# SCH_tenth-portenta-stack_2023-01-13.net
KiCad netlist of a schematic drawn in EasyEDA
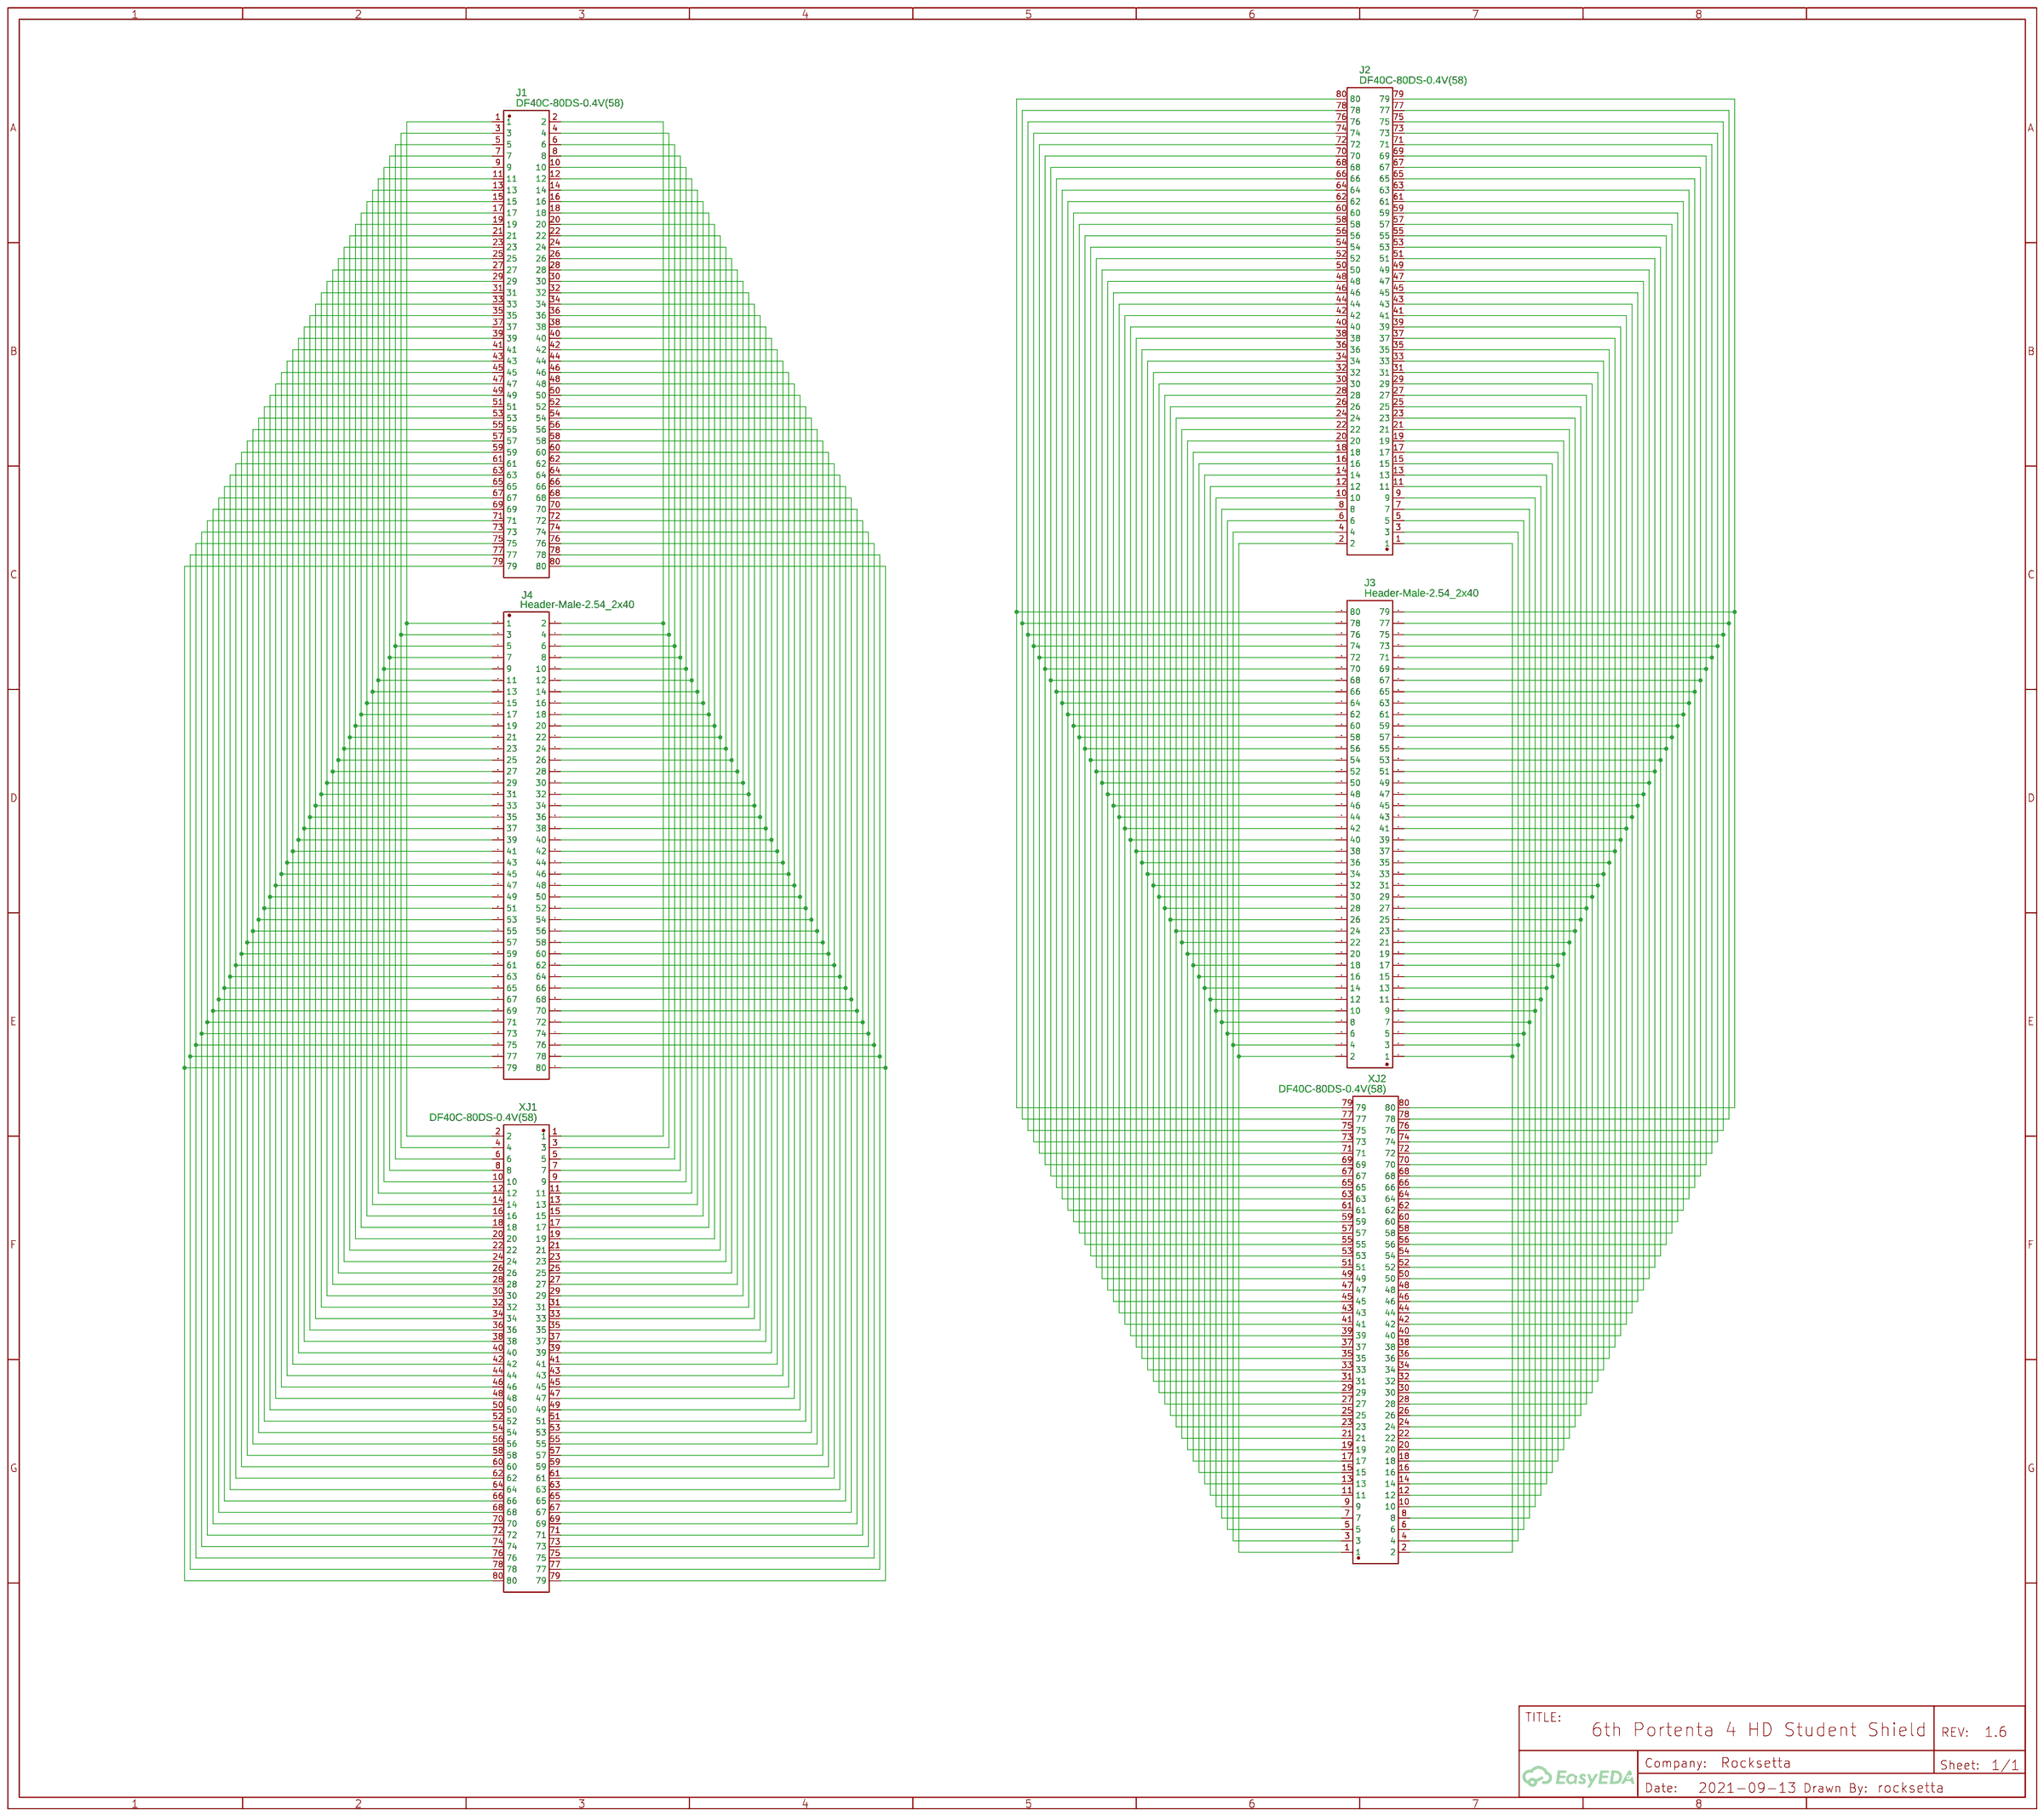
[diagram p0: schematic sheet]

(export (version "E")
  (design (tool "Eeschema 10.0.6"))
  (components
    (comp (ref "J1")
      (value "DF40C-80DS-0.4V(58)")
      (fields (field (name "BOM_Supplier Part") "C597941"))
      (libsource (lib "") (part "DF40C-80DS-0.4V(58)_1"))
    )
    (comp (ref "J2")
      (value "DF40C-80DS-0.4V(58)")
      (fields (field (name "BOM_Supplier Part") "C597941"))
      (libsource (lib "") (part "DF40C-80DS-0.4V(58)_2"))
    )
    (comp (ref "J3")
      (value "Header-Male-2.54_2x40")
      (fields
        (field (name "BOM_Manufacturer Part") "2.54mm 2x40P")
        (field (name "BOM_Supplier Part") "C2333")
      )
      (libsource (lib "") (part "Header-Male-2.54_2x40"))
    )
    (comp (ref "J4")
      (value "Header-Male-2.54_2x40")
      (fields
        (field (name "BOM_Manufacturer Part") "2.54mm 2x40P")
        (field (name "BOM_Supplier Part") "C2333")
      )
      (libsource (lib "") (part "Header-Male-2.54_2x40_1"))
    )
    (comp (ref "XJ1")
      (value "DF40C-80DS-0.4V(58)")
      (fields (field (name "BOM_Supplier Part") "C597941"))
      (libsource (lib "") (part "DF40C-80DS-0.4V(58)"))
    )
    (comp (ref "XJ2")
      (value "DF40C-80DS-0.4V(58)")
      (fields (field (name "BOM_Supplier Part") "C597941"))
      (libsource (lib "") (part "DF40C-80DS-0.4V(58)_3"))
    )
  )
  (nets
    (net (code "1") (name "Net-(J1-Pad1)") (class "Default")
      (node (ref "J1") (pin "1") (pinfunction "1_1") (pintype "unspecified"))
      (node (ref "J4") (pin "1") (pinfunction "1_1") (pintype "unspecified"))
      (node (ref "XJ1") (pin "2") (pinfunction "2_2") (pintype "unspecified"))
    )
    (net (code "2") (name "Net-(J1-Pad2)") (class "Default")
      (node (ref "J1") (pin "2") (pinfunction "2_2") (pintype "unspecified"))
      (node (ref "J4") (pin "2") (pinfunction "2_2") (pintype "unspecified"))
      (node (ref "XJ1") (pin "1") (pinfunction "1_1") (pintype "unspecified"))
    )
    (net (code "3") (name "Net-(J1-Pad3)") (class "Default")
      (node (ref "J1") (pin "3") (pinfunction "3_3") (pintype "unspecified"))
      (node (ref "J4") (pin "3") (pinfunction "3_3") (pintype "unspecified"))
      (node (ref "XJ1") (pin "4") (pinfunction "4_4") (pintype "unspecified"))
    )
    (net (code "4") (name "Net-(J1-Pad4)") (class "Default")
      (node (ref "J1") (pin "4") (pinfunction "4_4") (pintype "unspecified"))
      (node (ref "J4") (pin "4") (pinfunction "4_4") (pintype "unspecified"))
      (node (ref "XJ1") (pin "3") (pinfunction "3_3") (pintype "unspecified"))
    )
    (net (code "5") (name "Net-(J1-Pad5)") (class "Default")
      (node (ref "J1") (pin "5") (pinfunction "5_5") (pintype "unspecified"))
      (node (ref "J4") (pin "5") (pinfunction "5_5") (pintype "unspecified"))
      (node (ref "XJ1") (pin "6") (pinfunction "6_6") (pintype "unspecified"))
    )
    (net (code "6") (name "Net-(J1-Pad6)") (class "Default")
      (node (ref "J1") (pin "6") (pinfunction "6_6") (pintype "unspecified"))
      (node (ref "J4") (pin "6") (pinfunction "6_6") (pintype "unspecified"))
      (node (ref "XJ1") (pin "5") (pinfunction "5_5") (pintype "unspecified"))
    )
    (net (code "7") (name "Net-(J1-Pad7)") (class "Default")
      (node (ref "J1") (pin "7") (pinfunction "7_7") (pintype "unspecified"))
      (node (ref "J4") (pin "7") (pinfunction "7_7") (pintype "unspecified"))
      (node (ref "XJ1") (pin "8") (pinfunction "8_8") (pintype "unspecified"))
    )
    (net (code "8") (name "Net-(J1-Pad8)") (class "Default")
      (node (ref "J1") (pin "8") (pinfunction "8_8") (pintype "unspecified"))
      (node (ref "J4") (pin "8") (pinfunction "8_8") (pintype "unspecified"))
      (node (ref "XJ1") (pin "7") (pinfunction "7_7") (pintype "unspecified"))
    )
    (net (code "9") (name "Net-(J1-Pad9)") (class "Default")
      (node (ref "J1") (pin "9") (pinfunction "9_9") (pintype "unspecified"))
      (node (ref "J4") (pin "9") (pinfunction "9_9") (pintype "unspecified"))
      (node (ref "XJ1") (pin "10") (pinfunction "10_10") (pintype "unspecified"))
    )
    (net (code "10") (name "Net-(J1-Pad10)") (class "Default")
      (node (ref "J1") (pin "10") (pinfunction "10_10") (pintype "unspecified"))
      (node (ref "J4") (pin "10") (pinfunction "10_10") (pintype "unspecified"))
      (node (ref "XJ1") (pin "9") (pinfunction "9_9") (pintype "unspecified"))
    )
    (net (code "11") (name "Net-(J1-Pad11)") (class "Default")
      (node (ref "J1") (pin "11") (pinfunction "11_11") (pintype "unspecified"))
      (node (ref "J4") (pin "11") (pinfunction "11_11") (pintype "unspecified"))
      (node (ref "XJ1") (pin "12") (pinfunction "12_12") (pintype "unspecified"))
    )
    (net (code "12") (name "Net-(J1-Pad12)") (class "Default")
      (node (ref "J1") (pin "12") (pinfunction "12_12") (pintype "unspecified"))
      (node (ref "J4") (pin "12") (pinfunction "12_12") (pintype "unspecified"))
      (node (ref "XJ1") (pin "11") (pinfunction "11_11") (pintype "unspecified"))
    )
    (net (code "13") (name "Net-(J1-Pad13)") (class "Default")
      (node (ref "J1") (pin "13") (pinfunction "13_13") (pintype "unspecified"))
      (node (ref "J4") (pin "13") (pinfunction "13_13") (pintype "unspecified"))
      (node (ref "XJ1") (pin "14") (pinfunction "14_14") (pintype "unspecified"))
    )
    (net (code "14") (name "Net-(J1-Pad14)") (class "Default")
      (node (ref "J1") (pin "14") (pinfunction "14_14") (pintype "unspecified"))
      (node (ref "J4") (pin "14") (pinfunction "14_14") (pintype "unspecified"))
      (node (ref "XJ1") (pin "13") (pinfunction "13_13") (pintype "unspecified"))
    )
    (net (code "15") (name "Net-(J1-Pad15)") (class "Default")
      (node (ref "J1") (pin "15") (pinfunction "15_15") (pintype "unspecified"))
      (node (ref "J4") (pin "15") (pinfunction "15_15") (pintype "unspecified"))
      (node (ref "XJ1") (pin "16") (pinfunction "16_16") (pintype "unspecified"))
    )
    (net (code "16") (name "Net-(J1-Pad16)") (class "Default")
      (node (ref "J1") (pin "16") (pinfunction "16_16") (pintype "unspecified"))
      (node (ref "J4") (pin "16") (pinfunction "16_16") (pintype "unspecified"))
      (node (ref "XJ1") (pin "15") (pinfunction "15_15") (pintype "unspecified"))
    )
    (net (code "17") (name "Net-(J1-Pad17)") (class "Default")
      (node (ref "J1") (pin "17") (pinfunction "17_17") (pintype "unspecified"))
      (node (ref "J4") (pin "17") (pinfunction "17_17") (pintype "unspecified"))
      (node (ref "XJ1") (pin "18") (pinfunction "18_18") (pintype "unspecified"))
    )
    (net (code "18") (name "Net-(J1-Pad18)") (class "Default")
      (node (ref "J1") (pin "18") (pinfunction "18_18") (pintype "unspecified"))
      (node (ref "J4") (pin "18") (pinfunction "18_18") (pintype "unspecified"))
      (node (ref "XJ1") (pin "17") (pinfunction "17_17") (pintype "unspecified"))
    )
    (net (code "19") (name "Net-(J1-Pad19)") (class "Default")
      (node (ref "J1") (pin "19") (pinfunction "19_19") (pintype "unspecified"))
      (node (ref "J4") (pin "19") (pinfunction "19_19") (pintype "unspecified"))
      (node (ref "XJ1") (pin "20") (pinfunction "20_20") (pintype "unspecified"))
    )
    (net (code "20") (name "Net-(J1-Pad20)") (class "Default")
      (node (ref "J1") (pin "20") (pinfunction "20_20") (pintype "unspecified"))
      (node (ref "J4") (pin "20") (pinfunction "20_20") (pintype "unspecified"))
      (node (ref "XJ1") (pin "19") (pinfunction "19_19") (pintype "unspecified"))
    )
    (net (code "21") (name "Net-(J1-Pad21)") (class "Default")
      (node (ref "J1") (pin "21") (pinfunction "21_21") (pintype "unspecified"))
      (node (ref "J4") (pin "21") (pinfunction "21_21") (pintype "unspecified"))
      (node (ref "XJ1") (pin "22") (pinfunction "22_22") (pintype "unspecified"))
    )
    (net (code "22") (name "Net-(J1-Pad22)") (class "Default")
      (node (ref "J1") (pin "22") (pinfunction "22_22") (pintype "unspecified"))
      (node (ref "J4") (pin "22") (pinfunction "22_22") (pintype "unspecified"))
      (node (ref "XJ1") (pin "21") (pinfunction "21_21") (pintype "unspecified"))
    )
    (net (code "23") (name "Net-(J1-Pad23)") (class "Default")
      (node (ref "J1") (pin "23") (pinfunction "23_23") (pintype "unspecified"))
      (node (ref "J4") (pin "23") (pinfunction "23_23") (pintype "unspecified"))
      (node (ref "XJ1") (pin "24") (pinfunction "24_24") (pintype "unspecified"))
    )
    (net (code "24") (name "Net-(J1-Pad24)") (class "Default")
      (node (ref "J1") (pin "24") (pinfunction "24_24") (pintype "unspecified"))
      (node (ref "J4") (pin "24") (pinfunction "24_24") (pintype "unspecified"))
      (node (ref "XJ1") (pin "23") (pinfunction "23_23") (pintype "unspecified"))
    )
    (net (code "25") (name "Net-(J1-Pad25)") (class "Default")
      (node (ref "J1") (pin "25") (pinfunction "25_25") (pintype "unspecified"))
      (node (ref "J4") (pin "25") (pinfunction "25_25") (pintype "unspecified"))
      (node (ref "XJ1") (pin "26") (pinfunction "26_26") (pintype "unspecified"))
    )
    (net (code "26") (name "Net-(J1-Pad26)") (class "Default")
      (node (ref "J1") (pin "26") (pinfunction "26_26") (pintype "unspecified"))
      (node (ref "J4") (pin "26") (pinfunction "26_26") (pintype "unspecified"))
      (node (ref "XJ1") (pin "25") (pinfunction "25_25") (pintype "unspecified"))
    )
    (net (code "27") (name "Net-(J1-Pad27)") (class "Default")
      (node (ref "J1") (pin "27") (pinfunction "27_27") (pintype "unspecified"))
      (node (ref "J4") (pin "27") (pinfunction "27_27") (pintype "unspecified"))
      (node (ref "XJ1") (pin "28") (pinfunction "28_28") (pintype "unspecified"))
    )
    (net (code "28") (name "Net-(J1-Pad28)") (class "Default")
      (node (ref "J1") (pin "28") (pinfunction "28_28") (pintype "unspecified"))
      (node (ref "J4") (pin "28") (pinfunction "28_28") (pintype "unspecified"))
      (node (ref "XJ1") (pin "27") (pinfunction "27_27") (pintype "unspecified"))
    )
    (net (code "29") (name "Net-(J1-Pad29)") (class "Default")
      (node (ref "J1") (pin "29") (pinfunction "29_29") (pintype "unspecified"))
      (node (ref "J4") (pin "29") (pinfunction "29_29") (pintype "unspecified"))
      (node (ref "XJ1") (pin "30") (pinfunction "30_30") (pintype "unspecified"))
    )
    (net (code "30") (name "Net-(J1-Pad30)") (class "Default")
      (node (ref "J1") (pin "30") (pinfunction "30_30") (pintype "unspecified"))
      (node (ref "J4") (pin "30") (pinfunction "30_30") (pintype "unspecified"))
      (node (ref "XJ1") (pin "29") (pinfunction "29_29") (pintype "unspecified"))
    )
    (net (code "31") (name "Net-(J1-Pad31)") (class "Default")
      (node (ref "J1") (pin "31") (pinfunction "31_31") (pintype "unspecified"))
      (node (ref "J4") (pin "31") (pinfunction "31_31") (pintype "unspecified"))
      (node (ref "XJ1") (pin "32") (pinfunction "32_32") (pintype "unspecified"))
    )
    (net (code "32") (name "Net-(J1-Pad32)") (class "Default")
      (node (ref "J1") (pin "32") (pinfunction "32_32") (pintype "unspecified"))
      (node (ref "J4") (pin "32") (pinfunction "32_32") (pintype "unspecified"))
      (node (ref "XJ1") (pin "31") (pinfunction "31_31") (pintype "unspecified"))
    )
    (net (code "33") (name "Net-(J1-Pad33)") (class "Default")
      (node (ref "J1") (pin "33") (pinfunction "33_33") (pintype "unspecified"))
      (node (ref "J4") (pin "33") (pinfunction "33_33") (pintype "unspecified"))
      (node (ref "XJ1") (pin "34") (pinfunction "34_34") (pintype "unspecified"))
    )
    (net (code "34") (name "Net-(J1-Pad34)") (class "Default")
      (node (ref "J1") (pin "34") (pinfunction "34_34") (pintype "unspecified"))
      (node (ref "J4") (pin "34") (pinfunction "34_34") (pintype "unspecified"))
      (node (ref "XJ1") (pin "33") (pinfunction "33_33") (pintype "unspecified"))
    )
    (net (code "35") (name "Net-(J1-Pad35)") (class "Default")
      (node (ref "J1") (pin "35") (pinfunction "35_35") (pintype "unspecified"))
      (node (ref "J4") (pin "35") (pinfunction "35_35") (pintype "unspecified"))
      (node (ref "XJ1") (pin "36") (pinfunction "36_36") (pintype "unspecified"))
    )
    (net (code "36") (name "Net-(J1-Pad36)") (class "Default")
      (node (ref "J1") (pin "36") (pinfunction "36_36") (pintype "unspecified"))
      (node (ref "J4") (pin "36") (pinfunction "36_36") (pintype "unspecified"))
      (node (ref "XJ1") (pin "35") (pinfunction "35_35") (pintype "unspecified"))
    )
    (net (code "37") (name "Net-(J1-Pad37)") (class "Default")
      (node (ref "J1") (pin "37") (pinfunction "37_37") (pintype "unspecified"))
      (node (ref "J4") (pin "37") (pinfunction "37_37") (pintype "unspecified"))
      (node (ref "XJ1") (pin "38") (pinfunction "38_38") (pintype "unspecified"))
    )
    (net (code "38") (name "Net-(J1-Pad38)") (class "Default")
      (node (ref "J1") (pin "38") (pinfunction "38_38") (pintype "unspecified"))
      (node (ref "J4") (pin "38") (pinfunction "38_38") (pintype "unspecified"))
      (node (ref "XJ1") (pin "37") (pinfunction "37_37") (pintype "unspecified"))
    )
    (net (code "39") (name "Net-(J1-Pad39)") (class "Default")
      (node (ref "J1") (pin "39") (pinfunction "39_39") (pintype "unspecified"))
      (node (ref "J4") (pin "39") (pinfunction "39_39") (pintype "unspecified"))
      (node (ref "XJ1") (pin "40") (pinfunction "40_40") (pintype "unspecified"))
    )
    (net (code "40") (name "Net-(J1-Pad40)") (class "Default")
      (node (ref "J1") (pin "40") (pinfunction "40_40") (pintype "unspecified"))
      (node (ref "J4") (pin "40") (pinfunction "40_40") (pintype "unspecified"))
      (node (ref "XJ1") (pin "39") (pinfunction "39_39") (pintype "unspecified"))
    )
    (net (code "41") (name "Net-(J1-Pad41)") (class "Default")
      (node (ref "J1") (pin "41") (pinfunction "41_41") (pintype "unspecified"))
      (node (ref "J4") (pin "41") (pinfunction "41_41") (pintype "unspecified"))
      (node (ref "XJ1") (pin "42") (pinfunction "42_42") (pintype "unspecified"))
    )
    (net (code "42") (name "Net-(J1-Pad42)") (class "Default")
      (node (ref "J1") (pin "42") (pinfunction "42_42") (pintype "unspecified"))
      (node (ref "J4") (pin "42") (pinfunction "42_42") (pintype "unspecified"))
      (node (ref "XJ1") (pin "41") (pinfunction "41_41") (pintype "unspecified"))
    )
    (net (code "43") (name "Net-(J1-Pad43)") (class "Default")
      (node (ref "J1") (pin "43") (pinfunction "43_43") (pintype "unspecified"))
      (node (ref "J4") (pin "43") (pinfunction "43_43") (pintype "unspecified"))
      (node (ref "XJ1") (pin "44") (pinfunction "44_44") (pintype "unspecified"))
    )
    (net (code "44") (name "Net-(J1-Pad44)") (class "Default")
      (node (ref "J1") (pin "44") (pinfunction "44_44") (pintype "unspecified"))
      (node (ref "J4") (pin "44") (pinfunction "44_44") (pintype "unspecified"))
      (node (ref "XJ1") (pin "43") (pinfunction "43_43") (pintype "unspecified"))
    )
    (net (code "45") (name "Net-(J1-Pad45)") (class "Default")
      (node (ref "J1") (pin "45") (pinfunction "45_45") (pintype "unspecified"))
      (node (ref "J4") (pin "45") (pinfunction "45_45") (pintype "unspecified"))
      (node (ref "XJ1") (pin "46") (pinfunction "46_46") (pintype "unspecified"))
    )
    (net (code "46") (name "Net-(J1-Pad46)") (class "Default")
      (node (ref "J1") (pin "46") (pinfunction "46_46") (pintype "unspecified"))
      (node (ref "J4") (pin "46") (pinfunction "46_46") (pintype "unspecified"))
      (node (ref "XJ1") (pin "45") (pinfunction "45_45") (pintype "unspecified"))
    )
    (net (code "47") (name "Net-(J1-Pad47)") (class "Default")
      (node (ref "J1") (pin "47") (pinfunction "47_47") (pintype "unspecified"))
      (node (ref "J4") (pin "47") (pinfunction "47_47") (pintype "unspecified"))
      (node (ref "XJ1") (pin "48") (pinfunction "48_48") (pintype "unspecified"))
    )
    (net (code "48") (name "Net-(J1-Pad48)") (class "Default")
      (node (ref "J1") (pin "48") (pinfunction "48_48") (pintype "unspecified"))
      (node (ref "J4") (pin "48") (pinfunction "48_48") (pintype "unspecified"))
      (node (ref "XJ1") (pin "47") (pinfunction "47_47") (pintype "unspecified"))
    )
    (net (code "49") (name "Net-(J1-Pad49)") (class "Default")
      (node (ref "J1") (pin "49") (pinfunction "49_49") (pintype "unspecified"))
      (node (ref "J4") (pin "49") (pinfunction "49_49") (pintype "unspecified"))
      (node (ref "XJ1") (pin "50") (pinfunction "50_50") (pintype "unspecified"))
    )
    (net (code "50") (name "Net-(J1-Pad50)") (class "Default")
      (node (ref "J1") (pin "50") (pinfunction "50_50") (pintype "unspecified"))
      (node (ref "J4") (pin "50") (pinfunction "50_50") (pintype "unspecified"))
      (node (ref "XJ1") (pin "49") (pinfunction "49_49") (pintype "unspecified"))
    )
    (net (code "51") (name "Net-(J1-Pad51)") (class "Default")
      (node (ref "J1") (pin "51") (pinfunction "51_51") (pintype "unspecified"))
      (node (ref "J4") (pin "51") (pinfunction "51_51") (pintype "unspecified"))
      (node (ref "XJ1") (pin "52") (pinfunction "52_52") (pintype "unspecified"))
    )
    (net (code "52") (name "Net-(J1-Pad52)") (class "Default")
      (node (ref "J1") (pin "52") (pinfunction "52_52") (pintype "unspecified"))
      (node (ref "J4") (pin "52") (pinfunction "52_52") (pintype "unspecified"))
      (node (ref "XJ1") (pin "51") (pinfunction "51_51") (pintype "unspecified"))
    )
    (net (code "53") (name "Net-(J1-Pad53)") (class "Default")
      (node (ref "J1") (pin "53") (pinfunction "53_53") (pintype "unspecified"))
      (node (ref "J4") (pin "53") (pinfunction "53_53") (pintype "unspecified"))
      (node (ref "XJ1") (pin "54") (pinfunction "54_54") (pintype "unspecified"))
    )
    (net (code "54") (name "Net-(J1-Pad54)") (class "Default")
      (node (ref "J1") (pin "54") (pinfunction "54_54") (pintype "unspecified"))
      (node (ref "J4") (pin "54") (pinfunction "54_54") (pintype "unspecified"))
      (node (ref "XJ1") (pin "53") (pinfunction "53_53") (pintype "unspecified"))
    )
    (net (code "55") (name "Net-(J1-Pad55)") (class "Default")
      (node (ref "J1") (pin "55") (pinfunction "55_55") (pintype "unspecified"))
      (node (ref "J4") (pin "55") (pinfunction "55_55") (pintype "unspecified"))
      (node (ref "XJ1") (pin "56") (pinfunction "56_56") (pintype "unspecified"))
    )
    (net (code "56") (name "Net-(J1-Pad56)") (class "Default")
      (node (ref "J1") (pin "56") (pinfunction "56_56") (pintype "unspecified"))
      (node (ref "J4") (pin "56") (pinfunction "56_56") (pintype "unspecified"))
      (node (ref "XJ1") (pin "55") (pinfunction "55_55") (pintype "unspecified"))
    )
    (net (code "57") (name "Net-(J1-Pad57)") (class "Default")
      (node (ref "J1") (pin "57") (pinfunction "57_57") (pintype "unspecified"))
      (node (ref "J4") (pin "57") (pinfunction "57_57") (pintype "unspecified"))
      (node (ref "XJ1") (pin "58") (pinfunction "58_58") (pintype "unspecified"))
    )
    (net (code "58") (name "Net-(J1-Pad58)") (class "Default")
      (node (ref "J1") (pin "58") (pinfunction "58_58") (pintype "unspecified"))
      (node (ref "J4") (pin "58") (pinfunction "58_58") (pintype "unspecified"))
      (node (ref "XJ1") (pin "57") (pinfunction "57_57") (pintype "unspecified"))
    )
    (net (code "59") (name "Net-(J1-Pad59)") (class "Default")
      (node (ref "J1") (pin "59") (pinfunction "59_59") (pintype "unspecified"))
      (node (ref "J4") (pin "59") (pinfunction "59_59") (pintype "unspecified"))
      (node (ref "XJ1") (pin "60") (pinfunction "60_60") (pintype "unspecified"))
    )
    (net (code "60") (name "Net-(J1-Pad60)") (class "Default")
      (node (ref "J1") (pin "60") (pinfunction "60_60") (pintype "unspecified"))
      (node (ref "J4") (pin "60") (pinfunction "60_60") (pintype "unspecified"))
      (node (ref "XJ1") (pin "59") (pinfunction "59_59") (pintype "unspecified"))
    )
    (net (code "61") (name "Net-(J1-Pad61)") (class "Default")
      (node (ref "J1") (pin "61") (pinfunction "61_61") (pintype "unspecified"))
      (node (ref "J4") (pin "61") (pinfunction "61_61") (pintype "unspecified"))
      (node (ref "XJ1") (pin "62") (pinfunction "62_62") (pintype "unspecified"))
    )
    (net (code "62") (name "Net-(J1-Pad62)") (class "Default")
      (node (ref "J1") (pin "62") (pinfunction "62_62") (pintype "unspecified"))
      (node (ref "J4") (pin "62") (pinfunction "62_62") (pintype "unspecified"))
      (node (ref "XJ1") (pin "61") (pinfunction "61_61") (pintype "unspecified"))
    )
    (net (code "63") (name "Net-(J1-Pad63)") (class "Default")
      (node (ref "J1") (pin "63") (pinfunction "63_63") (pintype "unspecified"))
      (node (ref "J4") (pin "63") (pinfunction "63_63") (pintype "unspecified"))
      (node (ref "XJ1") (pin "64") (pinfunction "64_64") (pintype "unspecified"))
    )
    (net (code "64") (name "Net-(J1-Pad64)") (class "Default")
      (node (ref "J1") (pin "64") (pinfunction "64_64") (pintype "unspecified"))
      (node (ref "J4") (pin "64") (pinfunction "64_64") (pintype "unspecified"))
      (node (ref "XJ1") (pin "63") (pinfunction "63_63") (pintype "unspecified"))
    )
    (net (code "65") (name "Net-(J1-Pad65)") (class "Default")
      (node (ref "J1") (pin "65") (pinfunction "65_65") (pintype "unspecified"))
      (node (ref "J4") (pin "65") (pinfunction "65_65") (pintype "unspecified"))
      (node (ref "XJ1") (pin "66") (pinfunction "66_66") (pintype "unspecified"))
    )
    (net (code "66") (name "Net-(J1-Pad66)") (class "Default")
      (node (ref "J1") (pin "66") (pinfunction "66_66") (pintype "unspecified"))
      (node (ref "J4") (pin "66") (pinfunction "66_66") (pintype "unspecified"))
      (node (ref "XJ1") (pin "65") (pinfunction "65_65") (pintype "unspecified"))
    )
    (net (code "67") (name "Net-(J1-Pad67)") (class "Default")
      (node (ref "J1") (pin "67") (pinfunction "67_67") (pintype "unspecified"))
      (node (ref "J4") (pin "67") (pinfunction "67_67") (pintype "unspecified"))
      (node (ref "XJ1") (pin "68") (pinfunction "68_68") (pintype "unspecified"))
    )
    (net (code "68") (name "Net-(J1-Pad68)") (class "Default")
      (node (ref "J1") (pin "68") (pinfunction "68_68") (pintype "unspecified"))
      (node (ref "J4") (pin "68") (pinfunction "68_68") (pintype "unspecified"))
      (node (ref "XJ1") (pin "67") (pinfunction "67_67") (pintype "unspecified"))
    )
    (net (code "69") (name "Net-(J1-Pad69)") (class "Default")
      (node (ref "J1") (pin "69") (pinfunction "69_69") (pintype "unspecified"))
      (node (ref "J4") (pin "69") (pinfunction "69_69") (pintype "unspecified"))
      (node (ref "XJ1") (pin "70") (pinfunction "70_70") (pintype "unspecified"))
    )
    (net (code "70") (name "Net-(J1-Pad70)") (class "Default")
      (node (ref "J1") (pin "70") (pinfunction "70_70") (pintype "unspecified"))
      (node (ref "J4") (pin "70") (pinfunction "70_70") (pintype "unspecified"))
      (node (ref "XJ1") (pin "69") (pinfunction "69_69") (pintype "unspecified"))
    )
    (net (code "71") (name "Net-(J1-Pad71)") (class "Default")
      (node (ref "J1") (pin "71") (pinfunction "71_71") (pintype "unspecified"))
      (node (ref "J4") (pin "71") (pinfunction "71_71") (pintype "unspecified"))
      (node (ref "XJ1") (pin "72") (pinfunction "72_72") (pintype "unspecified"))
    )
    (net (code "72") (name "Net-(J1-Pad72)") (class "Default")
      (node (ref "J1") (pin "72") (pinfunction "72_72") (pintype "unspecified"))
      (node (ref "J4") (pin "72") (pinfunction "72_72") (pintype "unspecified"))
      (node (ref "XJ1") (pin "71") (pinfunction "71_71") (pintype "unspecified"))
    )
    (net (code "73") (name "Net-(J1-Pad73)") (class "Default")
      (node (ref "J1") (pin "73") (pinfunction "73_73") (pintype "unspecified"))
      (node (ref "J4") (pin "73") (pinfunction "73_73") (pintype "unspecified"))
      (node (ref "XJ1") (pin "74") (pinfunction "74_74") (pintype "unspecified"))
    )
    (net (code "74") (name "Net-(J1-Pad74)") (class "Default")
      (node (ref "J1") (pin "74") (pinfunction "74_74") (pintype "unspecified"))
      (node (ref "J4") (pin "74") (pinfunction "74_74") (pintype "unspecified"))
      (node (ref "XJ1") (pin "73") (pinfunction "73_73") (pintype "unspecified"))
    )
    (net (code "75") (name "Net-(J1-Pad75)") (class "Default")
      (node (ref "J1") (pin "75") (pinfunction "75_75") (pintype "unspecified"))
      (node (ref "J4") (pin "75") (pinfunction "75_75") (pintype "unspecified"))
      (node (ref "XJ1") (pin "76") (pinfunction "76_76") (pintype "unspecified"))
    )
    (net (code "76") (name "Net-(J1-Pad76)") (class "Default")
      (node (ref "J1") (pin "76") (pinfunction "76_76") (pintype "unspecified"))
      (node (ref "J4") (pin "76") (pinfunction "76_76") (pintype "unspecified"))
      (node (ref "XJ1") (pin "75") (pinfunction "75_75") (pintype "unspecified"))
    )
    (net (code "77") (name "Net-(J1-Pad77)") (class "Default")
      (node (ref "J1") (pin "77") (pinfunction "77_77") (pintype "unspecified"))
      (node (ref "J4") (pin "77") (pinfunction "77_77") (pintype "unspecified"))
      (node (ref "XJ1") (pin "78") (pinfunction "78_78") (pintype "unspecified"))
    )
    (net (code "78") (name "Net-(J1-Pad78)") (class "Default")
      (node (ref "J1") (pin "78") (pinfunction "78_78") (pintype "unspecified"))
      (node (ref "J4") (pin "78") (pinfunction "78_78") (pintype "unspecified"))
      (node (ref "XJ1") (pin "77") (pinfunction "77_77") (pintype "unspecified"))
    )
    (net (code "79") (name "Net-(J1-Pad79)") (class "Default")
      (node (ref "J1") (pin "79") (pinfunction "79_79") (pintype "unspecified"))
      (node (ref "J4") (pin "79") (pinfunction "79_79") (pintype "unspecified"))
      (node (ref "XJ1") (pin "80") (pinfunction "80_80") (pintype "unspecified"))
    )
    (net (code "80") (name "Net-(J1-Pad80)") (class "Default")
      (node (ref "J1") (pin "80") (pinfunction "80_80") (pintype "unspecified"))
      (node (ref "J4") (pin "80") (pinfunction "80_80") (pintype "unspecified"))
      (node (ref "XJ1") (pin "79") (pinfunction "79_79") (pintype "unspecified"))
    )
    (net (code "81") (name "Net-(J2-Pad1)") (class "Default")
      (node (ref "J2") (pin "1") (pinfunction "1_1") (pintype "unspecified"))
      (node (ref "J3") (pin "1") (pinfunction "1_1") (pintype "unspecified"))
      (node (ref "XJ2") (pin "2") (pinfunction "2_2") (pintype "unspecified"))
    )
    (net (code "82") (name "Net-(J2-Pad2)") (class "Default")
      (node (ref "J2") (pin "2") (pinfunction "2_2") (pintype "unspecified"))
      (node (ref "J3") (pin "2") (pinfunction "2_2") (pintype "unspecified"))
      (node (ref "XJ2") (pin "1") (pinfunction "1_1") (pintype "unspecified"))
    )
    (net (code "83") (name "Net-(J2-Pad3)") (class "Default")
      (node (ref "J2") (pin "3") (pinfunction "3_3") (pintype "unspecified"))
      (node (ref "J3") (pin "3") (pinfunction "3_3") (pintype "unspecified"))
      (node (ref "XJ2") (pin "4") (pinfunction "4_4") (pintype "unspecified"))
    )
    (net (code "84") (name "Net-(J2-Pad4)") (class "Default")
      (node (ref "J2") (pin "4") (pinfunction "4_4") (pintype "unspecified"))
      (node (ref "J3") (pin "4") (pinfunction "4_4") (pintype "unspecified"))
      (node (ref "XJ2") (pin "3") (pinfunction "3_3") (pintype "unspecified"))
    )
    (net (code "85") (name "Net-(J2-Pad5)") (class "Default")
      (node (ref "J2") (pin "5") (pinfunction "5_5") (pintype "unspecified"))
      (node (ref "J3") (pin "5") (pinfunction "5_5") (pintype "unspecified"))
      (node (ref "XJ2") (pin "6") (pinfunction "6_6") (pintype "unspecified"))
    )
    (net (code "86") (name "Net-(J2-Pad6)") (class "Default")
      (node (ref "J2") (pin "6") (pinfunction "6_6") (pintype "unspecified"))
      (node (ref "J3") (pin "6") (pinfunction "6_6") (pintype "unspecified"))
      (node (ref "XJ2") (pin "5") (pinfunction "5_5") (pintype "unspecified"))
    )
    (net (code "87") (name "Net-(J2-Pad7)") (class "Default")
      (node (ref "J2") (pin "7") (pinfunction "7_7") (pintype "unspecified"))
      (node (ref "J3") (pin "7") (pinfunction "7_7") (pintype "unspecified"))
      (node (ref "XJ2") (pin "8") (pinfunction "8_8") (pintype "unspecified"))
    )
    (net (code "88") (name "Net-(J2-Pad8)") (class "Default")
      (node (ref "J2") (pin "8") (pinfunction "8_8") (pintype "unspecified"))
      (node (ref "J3") (pin "8") (pinfunction "8_8") (pintype "unspecified"))
      (node (ref "XJ2") (pin "7") (pinfunction "7_7") (pintype "unspecified"))
    )
    (net (code "89") (name "Net-(J2-Pad9)") (class "Default")
      (node (ref "J2") (pin "9") (pinfunction "9_9") (pintype "unspecified"))
      (node (ref "J3") (pin "9") (pinfunction "9_9") (pintype "unspecified"))
      (node (ref "XJ2") (pin "10") (pinfunction "10_10") (pintype "unspecified"))
    )
    (net (code "90") (name "Net-(J2-Pad10)") (class "Default")
      (node (ref "J2") (pin "10") (pinfunction "10_10") (pintype "unspecified"))
      (node (ref "J3") (pin "10") (pinfunction "10_10") (pintype "unspecified"))
      (node (ref "XJ2") (pin "9") (pinfunction "9_9") (pintype "unspecified"))
    )
    (net (code "91") (name "Net-(J2-Pad11)") (class "Default")
      (node (ref "J2") (pin "11") (pinfunction "11_11") (pintype "unspecified"))
      (node (ref "J3") (pin "11") (pinfunction "11_11") (pintype "unspecified"))
      (node (ref "XJ2") (pin "12") (pinfunction "12_12") (pintype "unspecified"))
    )
    (net (code "92") (name "Net-(J2-Pad12)") (class "Default")
      (node (ref "J2") (pin "12") (pinfunction "12_12") (pintype "unspecified"))
      (node (ref "J3") (pin "12") (pinfunction "12_12") (pintype "unspecified"))
      (node (ref "XJ2") (pin "11") (pinfunction "11_11") (pintype "unspecified"))
    )
    (net (code "93") (name "Net-(J2-Pad13)") (class "Default")
      (node (ref "J2") (pin "13") (pinfunction "13_13") (pintype "unspecified"))
      (node (ref "J3") (pin "13") (pinfunction "13_13") (pintype "unspecified"))
      (node (ref "XJ2") (pin "14") (pinfunction "14_14") (pintype "unspecified"))
    )
    (net (code "94") (name "Net-(J2-Pad14)") (class "Default")
      (node (ref "J2") (pin "14") (pinfunction "14_14") (pintype "unspecified"))
      (node (ref "J3") (pin "14") (pinfunction "14_14") (pintype "unspecified"))
      (node (ref "XJ2") (pin "13") (pinfunction "13_13") (pintype "unspecified"))
    )
    (net (code "95") (name "Net-(J2-Pad15)") (class "Default")
      (node (ref "J2") (pin "15") (pinfunction "15_15") (pintype "unspecified"))
      (node (ref "J3") (pin "15") (pinfunction "15_15") (pintype "unspecified"))
      (node (ref "XJ2") (pin "16") (pinfunction "16_16") (pintype "unspecified"))
    )
    (net (code "96") (name "Net-(J2-Pad16)") (class "Default")
      (node (ref "J2") (pin "16") (pinfunction "16_16") (pintype "unspecified"))
      (node (ref "J3") (pin "16") (pinfunction "16_16") (pintype "unspecified"))
      (node (ref "XJ2") (pin "15") (pinfunction "15_15") (pintype "unspecified"))
    )
    (net (code "97") (name "Net-(J2-Pad17)") (class "Default")
      (node (ref "J2") (pin "17") (pinfunction "17_17") (pintype "unspecified"))
      (node (ref "J3") (pin "17") (pinfunction "17_17") (pintype "unspecified"))
      (node (ref "XJ2") (pin "18") (pinfunction "18_18") (pintype "unspecified"))
    )
    (net (code "98") (name "Net-(J2-Pad18)") (class "Default")
      (node (ref "J2") (pin "18") (pinfunction "18_18") (pintype "unspecified"))
      (node (ref "J3") (pin "18") (pinfunction "18_18") (pintype "unspecified"))
      (node (ref "XJ2") (pin "17") (pinfunction "17_17") (pintype "unspecified"))
    )
    (net (code "99") (name "Net-(J2-Pad19)") (class "Default")
      (node (ref "J2") (pin "19") (pinfunction "19_19") (pintype "unspecified"))
      (node (ref "J3") (pin "19") (pinfunction "19_19") (pintype "unspecified"))
      (node (ref "XJ2") (pin "20") (pinfunction "20_20") (pintype "unspecified"))
    )
    (net (code "100") (name "Net-(J2-Pad20)") (class "Default")
      (node (ref "J2") (pin "20") (pinfunction "20_20") (pintype "unspecified"))
      (node (ref "J3") (pin "20") (pinfunction "20_20") (pintype "unspecified"))
      (node (ref "XJ2") (pin "19") (pinfunction "19_19") (pintype "unspecified"))
    )
    (net (code "101") (name "Net-(J2-Pad21)") (class "Default")
      (node (ref "J2") (pin "21") (pinfunction "21_21") (pintype "unspecified"))
      (node (ref "J3") (pin "21") (pinfunction "21_21") (pintype "unspecified"))
      (node (ref "XJ2") (pin "22") (pinfunction "22_22") (pintype "unspecified"))
    )
    (net (code "102") (name "Net-(J2-Pad22)") (class "Default")
      (node (ref "J2") (pin "22") (pinfunction "22_22") (pintype "unspecified"))
      (node (ref "J3") (pin "22") (pinfunction "22_22") (pintype "unspecified"))
      (node (ref "XJ2") (pin "21") (pinfunction "21_21") (pintype "unspecified"))
    )
    (net (code "103") (name "Net-(J2-Pad23)") (class "Default")
      (node (ref "J2") (pin "23") (pinfunction "23_23") (pintype "unspecified"))
      (node (ref "J3") (pin "23") (pinfunction "23_23") (pintype "unspecified"))
      (node (ref "XJ2") (pin "24") (pinfunction "24_24") (pintype "unspecified"))
    )
    (net (code "104") (name "Net-(J2-Pad24)") (class "Default")
      (node (ref "J2") (pin "24") (pinfunction "24_24") (pintype "unspecified"))
      (node (ref "J3") (pin "24") (pinfunction "24_24") (pintype "unspecified"))
      (node (ref "XJ2") (pin "23") (pinfunction "23_23") (pintype "unspecified"))
    )
    (net (code "105") (name "Net-(J2-Pad25)") (class "Default")
      (node (ref "J2") (pin "25") (pinfunction "25_25") (pintype "unspecified"))
      (node (ref "J3") (pin "25") (pinfunction "25_25") (pintype "unspecified"))
      (node (ref "XJ2") (pin "26") (pinfunction "26_26") (pintype "unspecified"))
    )
    (net (code "106") (name "Net-(J2-Pad26)") (class "Default")
      (node (ref "J2") (pin "26") (pinfunction "26_26") (pintype "unspecified"))
      (node (ref "J3") (pin "26") (pinfunction "26_26") (pintype "unspecified"))
      (node (ref "XJ2") (pin "25") (pinfunction "25_25") (pintype "unspecified"))
    )
    (net (code "107") (name "Net-(J2-Pad27)") (class "Default")
      (node (ref "J2") (pin "27") (pinfunction "27_27") (pintype "unspecified"))
      (node (ref "J3") (pin "27") (pinfunction "27_27") (pintype "unspecified"))
      (node (ref "XJ2") (pin "28") (pinfunction "28_28") (pintype "unspecified"))
    )
    (net (code "108") (name "Net-(J2-Pad28)") (class "Default")
      (node (ref "J2") (pin "28") (pinfunction "28_28") (pintype "unspecified"))
      (node (ref "J3") (pin "28") (pinfunction "28_28") (pintype "unspecified"))
      (node (ref "XJ2") (pin "27") (pinfunction "27_27") (pintype "unspecified"))
    )
    (net (code "109") (name "Net-(J2-Pad29)") (class "Default")
      (node (ref "J2") (pin "29") (pinfunction "29_29") (pintype "unspecified"))
      (node (ref "J3") (pin "29") (pinfunction "29_29") (pintype "unspecified"))
      (node (ref "XJ2") (pin "30") (pinfunction "30_30") (pintype "unspecified"))
    )
    (net (code "110") (name "Net-(J2-Pad30)") (class "Default")
      (node (ref "J2") (pin "30") (pinfunction "30_30") (pintype "unspecified"))
      (node (ref "J3") (pin "30") (pinfunction "30_30") (pintype "unspecified"))
      (node (ref "XJ2") (pin "29") (pinfunction "29_29") (pintype "unspecified"))
    )
    (net (code "111") (name "Net-(J2-Pad31)") (class "Default")
      (node (ref "J2") (pin "31") (pinfunction "31_31") (pintype "unspecified"))
      (node (ref "J3") (pin "31") (pinfunction "31_31") (pintype "unspecified"))
      (node (ref "XJ2") (pin "32") (pinfunction "32_32") (pintype "unspecified"))
    )
    (net (code "112") (name "Net-(J2-Pad32)") (class "Default")
      (node (ref "J2") (pin "32") (pinfunction "32_32") (pintype "unspecified"))
      (node (ref "J3") (pin "32") (pinfunction "32_32") (pintype "unspecified"))
      (node (ref "XJ2") (pin "31") (pinfunction "31_31") (pintype "unspecified"))
    )
    (net (code "113") (name "Net-(J2-Pad33)") (class "Default")
      (node (ref "J2") (pin "33") (pinfunction "33_33") (pintype "unspecified"))
      (node (ref "J3") (pin "33") (pinfunction "33_33") (pintype "unspecified"))
      (node (ref "XJ2") (pin "34") (pinfunction "34_34") (pintype "unspecified"))
    )
    (net (code "114") (name "Net-(J2-Pad34)") (class "Default")
      (node (ref "J2") (pin "34") (pinfunction "34_34") (pintype "unspecified"))
      (node (ref "J3") (pin "34") (pinfunction "34_34") (pintype "unspecified"))
      (node (ref "XJ2") (pin "33") (pinfunction "33_33") (pintype "unspecified"))
    )
    (net (code "115") (name "Net-(J2-Pad35)") (class "Default")
      (node (ref "J2") (pin "35") (pinfunction "35_35") (pintype "unspecified"))
      (node (ref "J3") (pin "35") (pinfunction "35_35") (pintype "unspecified"))
      (node (ref "XJ2") (pin "36") (pinfunction "36_36") (pintype "unspecified"))
    )
    (net (code "116") (name "Net-(J2-Pad36)") (class "Default")
      (node (ref "J2") (pin "36") (pinfunction "36_36") (pintype "unspecified"))
      (node (ref "J3") (pin "36") (pinfunction "36_36") (pintype "unspecified"))
      (node (ref "XJ2") (pin "35") (pinfunction "35_35") (pintype "unspecified"))
    )
    (net (code "117") (name "Net-(J2-Pad37)") (class "Default")
      (node (ref "J2") (pin "37") (pinfunction "37_37") (pintype "unspecified"))
      (node (ref "J3") (pin "37") (pinfunction "37_37") (pintype "unspecified"))
      (node (ref "XJ2") (pin "38") (pinfunction "38_38") (pintype "unspecified"))
    )
    (net (code "118") (name "Net-(J2-Pad38)") (class "Default")
      (node (ref "J2") (pin "38") (pinfunction "38_38") (pintype "unspecified"))
      (node (ref "J3") (pin "38") (pinfunction "38_38") (pintype "unspecified"))
      (node (ref "XJ2") (pin "37") (pinfunction "37_37") (pintype "unspecified"))
    )
    (net (code "119") (name "Net-(J2-Pad39)") (class "Default")
      (node (ref "J2") (pin "39") (pinfunction "39_39") (pintype "unspecified"))
      (node (ref "J3") (pin "39") (pinfunction "39_39") (pintype "unspecified"))
      (node (ref "XJ2") (pin "40") (pinfunction "40_40") (pintype "unspecified"))
    )
    (net (code "120") (name "Net-(J2-Pad40)") (class "Default")
      (node (ref "J2") (pin "40") (pinfunction "40_40") (pintype "unspecified"))
      (node (ref "J3") (pin "40") (pinfunction "40_40") (pintype "unspecified"))
      (node (ref "XJ2") (pin "39") (pinfunction "39_39") (pintype "unspecified"))
    )
    (net (code "121") (name "Net-(J2-Pad41)") (class "Default")
      (node (ref "J2") (pin "41") (pinfunction "41_41") (pintype "unspecified"))
      (node (ref "J3") (pin "41") (pinfunction "41_41") (pintype "unspecified"))
      (node (ref "XJ2") (pin "42") (pinfunction "42_42") (pintype "unspecified"))
    )
    (net (code "122") (name "Net-(J2-Pad42)") (class "Default")
      (node (ref "J2") (pin "42") (pinfunction "42_42") (pintype "unspecified"))
      (node (ref "J3") (pin "42") (pinfunction "42_42") (pintype "unspecified"))
      (node (ref "XJ2") (pin "41") (pinfunction "41_41") (pintype "unspecified"))
    )
    (net (code "123") (name "Net-(J2-Pad43)") (class "Default")
      (node (ref "J2") (pin "43") (pinfunction "43_43") (pintype "unspecified"))
      (node (ref "J3") (pin "43") (pinfunction "43_43") (pintype "unspecified"))
      (node (ref "XJ2") (pin "44") (pinfunction "44_44") (pintype "unspecified"))
    )
    (net (code "124") (name "Net-(J2-Pad44)") (class "Default")
      (node (ref "J2") (pin "44") (pinfunction "44_44") (pintype "unspecified"))
      (node (ref "J3") (pin "44") (pinfunction "44_44") (pintype "unspecified"))
      (node (ref "XJ2") (pin "43") (pinfunction "43_43") (pintype "unspecified"))
    )
    (net (code "125") (name "Net-(J2-Pad45)") (class "Default")
      (node (ref "J2") (pin "45") (pinfunction "45_45") (pintype "unspecified"))
      (node (ref "J3") (pin "45") (pinfunction "45_45") (pintype "unspecified"))
      (node (ref "XJ2") (pin "46") (pinfunction "46_46") (pintype "unspecified"))
    )
    (net (code "126") (name "Net-(J2-Pad46)") (class "Default")
      (node (ref "J2") (pin "46") (pinfunction "46_46") (pintype "unspecified"))
      (node (ref "J3") (pin "46") (pinfunction "46_46") (pintype "unspecified"))
      (node (ref "XJ2") (pin "45") (pinfunction "45_45") (pintype "unspecified"))
    )
    (net (code "127") (name "Net-(J2-Pad47)") (class "Default")
      (node (ref "J2") (pin "47") (pinfunction "47_47") (pintype "unspecified"))
      (node (ref "J3") (pin "47") (pinfunction "47_47") (pintype "unspecified"))
      (node (ref "XJ2") (pin "48") (pinfunction "48_48") (pintype "unspecified"))
    )
    (net (code "128") (name "Net-(J2-Pad48)") (class "Default")
      (node (ref "J2") (pin "48") (pinfunction "48_48") (pintype "unspecified"))
      (node (ref "J3") (pin "48") (pinfunction "48_48") (pintype "unspecified"))
      (node (ref "XJ2") (pin "47") (pinfunction "47_47") (pintype "unspecified"))
    )
    (net (code "129") (name "Net-(J2-Pad49)") (class "Default")
      (node (ref "J2") (pin "49") (pinfunction "49_49") (pintype "unspecified"))
      (node (ref "J3") (pin "49") (pinfunction "49_49") (pintype "unspecified"))
      (node (ref "XJ2") (pin "50") (pinfunction "50_50") (pintype "unspecified"))
    )
    (net (code "130") (name "Net-(J2-Pad50)") (class "Default")
      (node (ref "J2") (pin "50") (pinfunction "50_50") (pintype "unspecified"))
      (node (ref "J3") (pin "50") (pinfunction "50_50") (pintype "unspecified"))
      (node (ref "XJ2") (pin "49") (pinfunction "49_49") (pintype "unspecified"))
    )
    (net (code "131") (name "Net-(J2-Pad51)") (class "Default")
      (node (ref "J2") (pin "51") (pinfunction "51_51") (pintype "unspecified"))
      (node (ref "J3") (pin "51") (pinfunction "51_51") (pintype "unspecified"))
      (node (ref "XJ2") (pin "52") (pinfunction "52_52") (pintype "unspecified"))
    )
    (net (code "132") (name "Net-(J2-Pad52)") (class "Default")
      (node (ref "J2") (pin "52") (pinfunction "52_52") (pintype "unspecified"))
      (node (ref "J3") (pin "52") (pinfunction "52_52") (pintype "unspecified"))
      (node (ref "XJ2") (pin "51") (pinfunction "51_51") (pintype "unspecified"))
    )
    (net (code "133") (name "Net-(J2-Pad53)") (class "Default")
      (node (ref "J2") (pin "53") (pinfunction "53_53") (pintype "unspecified"))
      (node (ref "J3") (pin "53") (pinfunction "53_53") (pintype "unspecified"))
      (node (ref "XJ2") (pin "54") (pinfunction "54_54") (pintype "unspecified"))
    )
    (net (code "134") (name "Net-(J2-Pad54)") (class "Default")
      (node (ref "J2") (pin "54") (pinfunction "54_54") (pintype "unspecified"))
      (node (ref "J3") (pin "54") (pinfunction "54_54") (pintype "unspecified"))
      (node (ref "XJ2") (pin "53") (pinfunction "53_53") (pintype "unspecified"))
    )
    (net (code "135") (name "Net-(J2-Pad55)") (class "Default")
      (node (ref "J2") (pin "55") (pinfunction "55_55") (pintype "unspecified"))
      (node (ref "J3") (pin "55") (pinfunction "55_55") (pintype "unspecified"))
      (node (ref "XJ2") (pin "56") (pinfunction "56_56") (pintype "unspecified"))
    )
    (net (code "136") (name "Net-(J2-Pad56)") (class "Default")
      (node (ref "J2") (pin "56") (pinfunction "56_56") (pintype "unspecified"))
      (node (ref "J3") (pin "56") (pinfunction "56_56") (pintype "unspecified"))
      (node (ref "XJ2") (pin "55") (pinfunction "55_55") (pintype "unspecified"))
    )
    (net (code "137") (name "Net-(J2-Pad57)") (class "Default")
      (node (ref "J2") (pin "57") (pinfunction "57_57") (pintype "unspecified"))
      (node (ref "J3") (pin "57") (pinfunction "57_57") (pintype "unspecified"))
      (node (ref "XJ2") (pin "58") (pinfunction "58_58") (pintype "unspecified"))
    )
    (net (code "138") (name "Net-(J2-Pad58)") (class "Default")
      (node (ref "J2") (pin "58") (pinfunction "58_58") (pintype "unspecified"))
      (node (ref "J3") (pin "58") (pinfunction "58_58") (pintype "unspecified"))
      (node (ref "XJ2") (pin "57") (pinfunction "57_57") (pintype "unspecified"))
    )
    (net (code "139") (name "Net-(J2-Pad59)") (class "Default")
      (node (ref "J2") (pin "59") (pinfunction "59_59") (pintype "unspecified"))
      (node (ref "J3") (pin "59") (pinfunction "59_59") (pintype "unspecified"))
      (node (ref "XJ2") (pin "60") (pinfunction "60_60") (pintype "unspecified"))
    )
    (net (code "140") (name "Net-(J2-Pad60)") (class "Default")
      (node (ref "J2") (pin "60") (pinfunction "60_60") (pintype "unspecified"))
      (node (ref "J3") (pin "60") (pinfunction "60_60") (pintype "unspecified"))
      (node (ref "XJ2") (pin "59") (pinfunction "59_59") (pintype "unspecified"))
    )
    (net (code "141") (name "Net-(J2-Pad61)") (class "Default")
      (node (ref "J2") (pin "61") (pinfunction "61_61") (pintype "unspecified"))
      (node (ref "J3") (pin "61") (pinfunction "61_61") (pintype "unspecified"))
      (node (ref "XJ2") (pin "62") (pinfunction "62_62") (pintype "unspecified"))
    )
    (net (code "142") (name "Net-(J2-Pad62)") (class "Default")
      (node (ref "J2") (pin "62") (pinfunction "62_62") (pintype "unspecified"))
      (node (ref "J3") (pin "62") (pinfunction "62_62") (pintype "unspecified"))
      (node (ref "XJ2") (pin "61") (pinfunction "61_61") (pintype "unspecified"))
    )
    (net (code "143") (name "Net-(J2-Pad63)") (class "Default")
      (node (ref "J2") (pin "63") (pinfunction "63_63") (pintype "unspecified"))
      (node (ref "J3") (pin "63") (pinfunction "63_63") (pintype "unspecified"))
      (node (ref "XJ2") (pin "64") (pinfunction "64_64") (pintype "unspecified"))
    )
    (net (code "144") (name "Net-(J2-Pad64)") (class "Default")
      (node (ref "J2") (pin "64") (pinfunction "64_64") (pintype "unspecified"))
      (node (ref "J3") (pin "64") (pinfunction "64_64") (pintype "unspecified"))
      (node (ref "XJ2") (pin "63") (pinfunction "63_63") (pintype "unspecified"))
    )
    (net (code "145") (name "Net-(J2-Pad65)") (class "Default")
      (node (ref "J2") (pin "65") (pinfunction "65_65") (pintype "unspecified"))
      (node (ref "J3") (pin "65") (pinfunction "65_65") (pintype "unspecified"))
      (node (ref "XJ2") (pin "66") (pinfunction "66_66") (pintype "unspecified"))
    )
    (net (code "146") (name "Net-(J2-Pad66)") (class "Default")
      (node (ref "J2") (pin "66") (pinfunction "66_66") (pintype "unspecified"))
      (node (ref "J3") (pin "66") (pinfunction "66_66") (pintype "unspecified"))
      (node (ref "XJ2") (pin "65") (pinfunction "65_65") (pintype "unspecified"))
    )
    (net (code "147") (name "Net-(J2-Pad67)") (class "Default")
      (node (ref "J2") (pin "67") (pinfunction "67_67") (pintype "unspecified"))
      (node (ref "J3") (pin "67") (pinfunction "67_67") (pintype "unspecified"))
      (node (ref "XJ2") (pin "68") (pinfunction "68_68") (pintype "unspecified"))
    )
    (net (code "148") (name "Net-(J2-Pad68)") (class "Default")
      (node (ref "J2") (pin "68") (pinfunction "68_68") (pintype "unspecified"))
      (node (ref "J3") (pin "68") (pinfunction "68_68") (pintype "unspecified"))
      (node (ref "XJ2") (pin "67") (pinfunction "67_67") (pintype "unspecified"))
    )
    (net (code "149") (name "Net-(J2-Pad69)") (class "Default")
      (node (ref "J2") (pin "69") (pinfunction "69_69") (pintype "unspecified"))
      (node (ref "J3") (pin "69") (pinfunction "69_69") (pintype "unspecified"))
      (node (ref "XJ2") (pin "70") (pinfunction "70_70") (pintype "unspecified"))
    )
    (net (code "150") (name "Net-(J2-Pad70)") (class "Default")
      (node (ref "J2") (pin "70") (pinfunction "70_70") (pintype "unspecified"))
      (node (ref "J3") (pin "70") (pinfunction "70_70") (pintype "unspecified"))
      (node (ref "XJ2") (pin "69") (pinfunction "69_69") (pintype "unspecified"))
    )
    (net (code "151") (name "Net-(J2-Pad71)") (class "Default")
      (node (ref "J2") (pin "71") (pinfunction "71_71") (pintype "unspecified"))
      (node (ref "J3") (pin "71") (pinfunction "71_71") (pintype "unspecified"))
      (node (ref "XJ2") (pin "72") (pinfunction "72_72") (pintype "unspecified"))
    )
    (net (code "152") (name "Net-(J2-Pad72)") (class "Default")
      (node (ref "J2") (pin "72") (pinfunction "72_72") (pintype "unspecified"))
      (node (ref "J3") (pin "72") (pinfunction "72_72") (pintype "unspecified"))
      (node (ref "XJ2") (pin "71") (pinfunction "71_71") (pintype "unspecified"))
    )
    (net (code "153") (name "Net-(J2-Pad73)") (class "Default")
      (node (ref "J2") (pin "73") (pinfunction "73_73") (pintype "unspecified"))
      (node (ref "J3") (pin "73") (pinfunction "73_73") (pintype "unspecified"))
      (node (ref "XJ2") (pin "74") (pinfunction "74_74") (pintype "unspecified"))
    )
    (net (code "154") (name "Net-(J2-Pad74)") (class "Default")
      (node (ref "J2") (pin "74") (pinfunction "74_74") (pintype "unspecified"))
      (node (ref "J3") (pin "74") (pinfunction "74_74") (pintype "unspecified"))
      (node (ref "XJ2") (pin "73") (pinfunction "73_73") (pintype "unspecified"))
    )
    (net (code "155") (name "Net-(J2-Pad75)") (class "Default")
      (node (ref "J2") (pin "75") (pinfunction "75_75") (pintype "unspecified"))
      (node (ref "J3") (pin "75") (pinfunction "75_75") (pintype "unspecified"))
      (node (ref "XJ2") (pin "76") (pinfunction "76_76") (pintype "unspecified"))
    )
    (net (code "156") (name "Net-(J2-Pad76)") (class "Default")
      (node (ref "J2") (pin "76") (pinfunction "76_76") (pintype "unspecified"))
      (node (ref "J3") (pin "76") (pinfunction "76_76") (pintype "unspecified"))
      (node (ref "XJ2") (pin "75") (pinfunction "75_75") (pintype "unspecified"))
    )
    (net (code "157") (name "Net-(J2-Pad77)") (class "Default")
      (node (ref "J2") (pin "77") (pinfunction "77_77") (pintype "unspecified"))
      (node (ref "J3") (pin "77") (pinfunction "77_77") (pintype "unspecified"))
      (node (ref "XJ2") (pin "78") (pinfunction "78_78") (pintype "unspecified"))
    )
    (net (code "158") (name "Net-(J2-Pad78)") (class "Default")
      (node (ref "J2") (pin "78") (pinfunction "78_78") (pintype "unspecified"))
      (node (ref "J3") (pin "78") (pinfunction "78_78") (pintype "unspecified"))
      (node (ref "XJ2") (pin "77") (pinfunction "77_77") (pintype "unspecified"))
    )
    (net (code "159") (name "Net-(J2-Pad79)") (class "Default")
      (node (ref "J2") (pin "79") (pinfunction "79_79") (pintype "unspecified"))
      (node (ref "J3") (pin "79") (pinfunction "79_79") (pintype "unspecified"))
      (node (ref "XJ2") (pin "80") (pinfunction "80_80") (pintype "unspecified"))
    )
    (net (code "160") (name "Net-(J2-Pad80)") (class "Default")
      (node (ref "J2") (pin "80") (pinfunction "80_80") (pintype "unspecified"))
      (node (ref "J3") (pin "80") (pinfunction "80_80") (pintype "unspecified"))
      (node (ref "XJ2") (pin "79") (pinfunction "79_79") (pintype "unspecified"))
    )
  )
)
